# triode_system_board.net
KiCad netlist of a schematic drawn in EAGLE
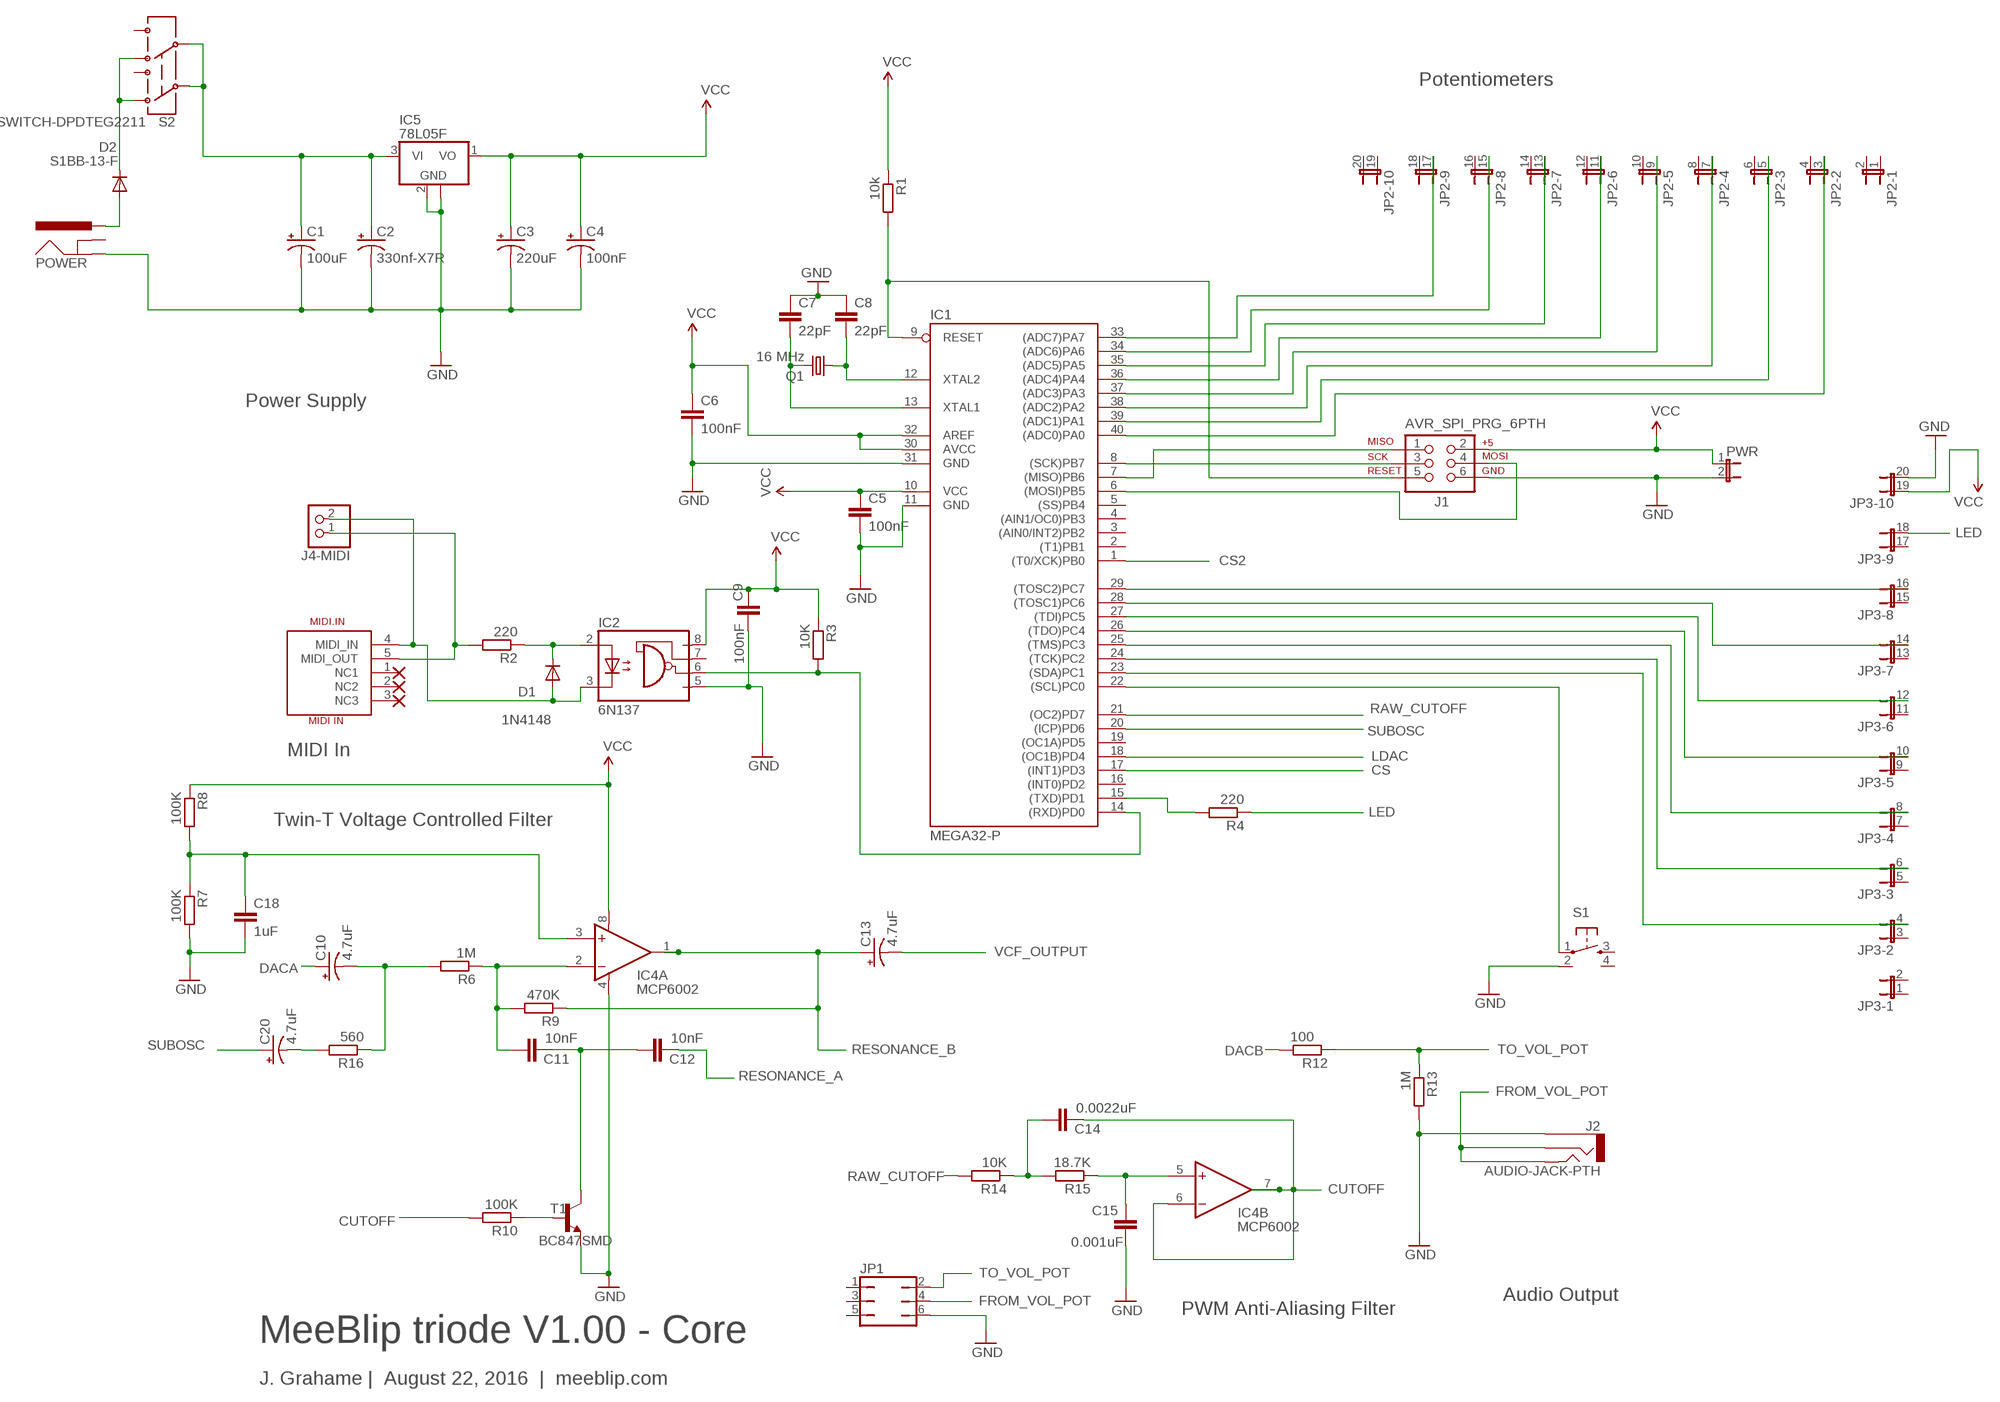
[diagram p0: schematic, sheet 1]
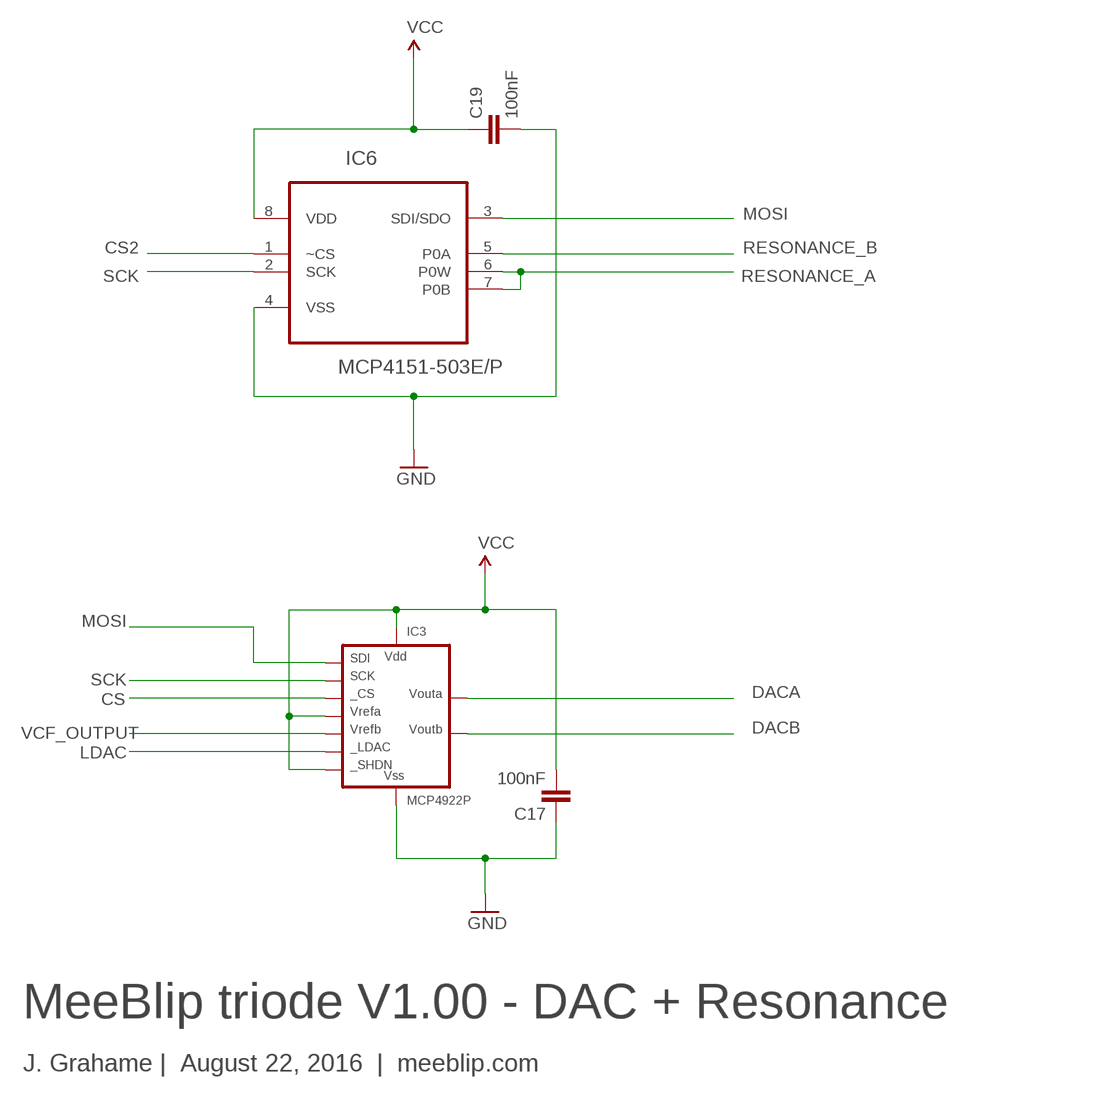
[diagram p1: schematic, sheet 2]

(export (version "E")
  (design (tool "Eeschema 10.0.6"))
  (components
    (comp (ref "C1")
      (value "100uF")
      (footprint "eagle-import:PANASONIC_D")
      (libsource (lib "eagle-import") (part "CAP_POLD"))
    )
    (comp (ref "C2")
      (value "330nf-X7R")
      (footprint "eagle-import:PANASONIC_C")
      (libsource (lib "eagle-import") (part "CAP_POLC"))
    )
    (comp (ref "C3")
      (value "220uF")
      (footprint "eagle-import:PANASONIC_D")
      (libsource (lib "eagle-import") (part "CAP_POLD"))
    )
    (comp (ref "C4")
      (value "100nF")
      (footprint "eagle-import:PANASONIC_C")
      (libsource (lib "eagle-import") (part "CAP_POLC"))
    )
    (comp (ref "C5")
      (value "100nF")
      (footprint "eagle-import:0603-CAP")
      (libsource (lib "eagle-import") (part "CAP0603-CAP"))
    )
    (comp (ref "C6")
      (value "100nF")
      (footprint "eagle-import:0603-CAP")
      (libsource (lib "eagle-import") (part "CAP0603-CAP"))
    )
    (comp (ref "C7")
      (value "22pF")
      (footprint "eagle-import:0603-CAP")
      (libsource (lib "eagle-import") (part "CAP0603-CAP"))
    )
    (comp (ref "C8")
      (value "22pF")
      (footprint "eagle-import:0603-CAP")
      (libsource (lib "eagle-import") (part "CAP0603-CAP"))
    )
    (comp (ref "C9")
      (value "100nF")
      (footprint "eagle-import:0603-CAP")
      (libsource (lib "eagle-import") (part "CAP0603-CAP"))
    )
    (comp (ref "C10")
      (value "4.7uF")
      (footprint "eagle-import:PANASONIC_C")
      (libsource (lib "eagle-import") (part "CAP_POLC"))
    )
    (comp (ref "C11")
      (value "10nF")
      (footprint "eagle-import:0603-CAP")
      (libsource (lib "eagle-import") (part "CAP0603-CAP"))
    )
    (comp (ref "C12")
      (value "10nF")
      (footprint "eagle-import:0603-CAP")
      (libsource (lib "eagle-import") (part "CAP0603-CAP"))
    )
    (comp (ref "C13")
      (value "4.7uF")
      (footprint "eagle-import:PANASONIC_C")
      (libsource (lib "eagle-import") (part "CAP_POLC"))
    )
    (comp (ref "C14")
      (value "0.0022uF")
      (footprint "eagle-import:0603-CAP")
      (libsource (lib "eagle-import") (part "CAP0603-CAP"))
    )
    (comp (ref "C15")
      (value "0.001uF")
      (footprint "eagle-import:0603-CAP")
      (libsource (lib "eagle-import") (part "CAP0603-CAP"))
    )
    (comp (ref "C18")
      (value "1uF")
      (footprint "eagle-import:0603-CAP")
      (libsource (lib "eagle-import") (part "CAP0603-CAP"))
    )
    (comp (ref "C20")
      (value "4.7uF")
      (footprint "eagle-import:PANASONIC_C")
      (libsource (lib "eagle-import") (part "CAP_POLC"))
    )
    (comp (ref "D1")
      (value "1N4148")
      (footprint "eagle-import:SOD123")
      (libsource (lib "eagle-import") (part "DIODE-SOD123"))
    )
    (comp (ref "D2")
      (value "S1BB-13-F")
      (footprint "eagle-import:SMA-DO214AC")
      (libsource (lib "eagle-import") (part "GF1"))
    )
    (comp (ref "IC1")
      (value "MEGA32-P")
      (footprint "eagle-import:DIL40")
      (fields (field (name "MPN") "ATMEGA32-16PU"))
      (libsource (lib "eagle-import") (part "MEGA32-P"))
    )
    (comp (ref "IC2")
      (value "6N137")
      (footprint "eagle-import:DIL08")
      (libsource (lib "eagle-import") (part "6N137"))
    )
    (comp (ref "IC4")
      (value "MCP6002")
      (footprint "eagle-import:DIL08")
      (libsource (lib "eagle-import") (part "MCP6002"))
    )
    (comp (ref "IC5")
      (value "78L05F")
      (footprint "eagle-import:SOT89")
      (libsource (lib "eagle-import") (part "78LF05"))
    )
    (comp (ref "J1")
      (value "AVR_SPI_PRG_6PTH")
      (footprint "eagle-import:2X3")
      (libsource (lib "eagle-import") (part "AVR_SPI_PRG_6PTH"))
    )
    (comp (ref "J2")
      (value "AUDIO-JACK-PTH")
      (footprint "eagle-import:AUDIO-JACK")
      (libsource (lib "eagle-import") (part "AUDIO-JACK-PTH"))
    )
    (comp (ref "J4-MIDI")
      (value "PINHD-1X2")
      (footprint "eagle-import:1X02")
      (libsource (lib "eagle-import") (part "PINHD-1X2"))
    )
    (comp (ref "JP1")
      (value "JP3Q")
      (footprint "eagle-import:JP3Q")
      (libsource (lib "eagle-import") (part "JP3Q"))
    )
    (comp (ref "JP2")
      (value "JP10QE")
      (footprint "eagle-import:JP10Q")
      (libsource (lib "eagle-import") (part "JP10QE"))
    )
    (comp (ref "JP3")
      (value "JP10QE")
      (footprint "eagle-import:JP10Q")
      (libsource (lib "eagle-import") (part "JP10QE"))
    )
    (comp (ref "MIDI.IN")
      (value "MIDI IN")
      (footprint "eagle-import:DIN_5_FEMALE_SUPPORT")
      (libsource (lib "eagle-import") (part "MIDI_CONN_FEMALE_SUPPORT"))
    )
    (comp (ref "POWER")
      (value "POWER_JACKPTH")
      (footprint "eagle-import:POWER_JACK_PTH")
      (libsource (lib "eagle-import") (part "POWER_JACKPTH"))
    )
    (comp (ref "PWR")
      (value "JUMPER-2PTH")
      (footprint "eagle-import:1X02")
      (libsource (lib "eagle-import") (part "JUMPER-2PTH"))
    )
    (comp (ref "Q1")
      (value "16 MHz")
      (footprint "eagle-import:HC49UP")
      (libsource (lib "eagle-import") (part "CRYSTALSMD"))
    )
    (comp (ref "R1")
      (value "10k")
      (footprint "eagle-import:M1206")
      (libsource (lib "eagle-import") (part "R-EU_M1206"))
    )
    (comp (ref "R2")
      (value "220")
      (footprint "eagle-import:M1206")
      (libsource (lib "eagle-import") (part "R-EU_M1206"))
    )
    (comp (ref "R3")
      (value "10K")
      (footprint "eagle-import:M1206")
      (libsource (lib "eagle-import") (part "R-EU_M1206"))
    )
    (comp (ref "R4")
      (value "220")
      (footprint "eagle-import:M1206")
      (libsource (lib "eagle-import") (part "R-EU_M1206"))
    )
    (comp (ref "R6")
      (value "1M")
      (footprint "eagle-import:M1206")
      (libsource (lib "eagle-import") (part "R-EU_M1206"))
    )
    (comp (ref "R7")
      (value "100K")
      (footprint "eagle-import:M1206")
      (libsource (lib "eagle-import") (part "R-EU_M1206"))
    )
    (comp (ref "R8")
      (value "100K")
      (footprint "eagle-import:M1206")
      (libsource (lib "eagle-import") (part "R-EU_M1206"))
    )
    (comp (ref "R9")
      (value "470K")
      (footprint "eagle-import:M1206")
      (libsource (lib "eagle-import") (part "R-EU_M1206"))
    )
    (comp (ref "R10")
      (value "100K")
      (footprint "eagle-import:M1206")
      (libsource (lib "eagle-import") (part "R-EU_M1206"))
    )
    (comp (ref "R12")
      (value "100")
      (footprint "eagle-import:M1206")
      (libsource (lib "eagle-import") (part "R-EU_M1206"))
    )
    (comp (ref "R13")
      (value "1M")
      (footprint "eagle-import:M1206")
      (libsource (lib "eagle-import") (part "R-EU_M1206"))
    )
    (comp (ref "R14")
      (value "10K")
      (footprint "eagle-import:M1206")
      (libsource (lib "eagle-import") (part "R-EU_M1206"))
    )
    (comp (ref "R15")
      (value "18.7K")
      (footprint "eagle-import:M1206")
      (libsource (lib "eagle-import") (part "R-EU_M1206"))
    )
    (comp (ref "R16")
      (value "560")
      (footprint "eagle-import:M1206")
      (libsource (lib "eagle-import") (part "R-EU_M1206"))
    )
    (comp (ref "S1")
      (value "TAC_SWITCHPTH")
      (footprint "eagle-import:TACTILE-PTH")
      (libsource (lib "eagle-import") (part "TAC_SWITCHPTH"))
    )
    (comp (ref "S2")
      (value "SWITCH-DPDTEG2211")
      (footprint "eagle-import:EG2208A")
      (libsource (lib "eagle-import") (part "SWITCH-DPDTEG2211"))
    )
    (comp (ref "T1")
      (value "BC847SMD")
      (footprint "eagle-import:SOT23")
      (libsource (lib "eagle-import") (part "BC847SMD"))
    )
    (comp (ref "C17")
      (value "100nF")
      (footprint "eagle-import:0603-CAP")
      (libsource (lib "eagle-import") (part "CAP0603-CAP"))
    )
    (comp (ref "C19")
      (value "100nF")
      (footprint "eagle-import:0603-CAP")
      (libsource (lib "eagle-import") (part "CAP0603-CAP"))
    )
    (comp (ref "IC3")
      (value "MCP4922P")
      (footprint "eagle-import:DIL14")
      (libsource (lib "eagle-import") (part "MCP4922P"))
    )
    (comp (ref "IC6")
      (value "MCP4151-503E/P")
      (footprint "eagle-import:DIP254P762X533-8")
      (libsource (lib "eagle-import") (part "MCP4151-503E/P"))
    )
  )
  (nets
    (net (code "1") (name "CS") (class "Default")
      (node (ref "IC1") (pin "17") (pinfunction "(INT1)PD3_17") (pintype "bidirectional"))
      (node (ref "IC3") (pin "3") (pinfunction "CS_3") (pintype "input"))
    )
    (net (code "2") (name "CS2") (class "Default")
      (node (ref "IC1") (pin "1") (pinfunction "(T0/XCK)PB0_1") (pintype "bidirectional"))
      (node (ref "IC6") (pin "1") (pinfunction "~{CS}_1") (pintype "input"))
    )
    (net (code "3") (name "CUTOFF") (class "Default")
      (node (ref "C14") (pin "2") (pinfunction "2_2") (pintype "passive"))
      (node (ref "IC4") (pin "6") (pinfunction "-IN_6") (pintype "input"))
      (node (ref "IC4") (pin "7") (pinfunction "OUT_7") (pintype "output"))
      (node (ref "R10") (pin "2") (pinfunction "2_2") (pintype "passive"))
    )
    (net (code "4") (name "DACA") (class "Default")
      (node (ref "C10") (pin "+") (pinfunction "+_+") (pintype "passive"))
      (node (ref "IC3") (pin "14") (pinfunction "VOUTA_14") (pintype "output"))
    )
    (net (code "5") (name "DACB") (class "Default")
      (node (ref "IC3") (pin "10") (pinfunction "VOUTB_10") (pintype "output"))
      (node (ref "R12") (pin "2") (pinfunction "2_2") (pintype "passive"))
    )
    (net (code "6") (name "FROM_VOL_POT") (class "Default")
      (node (ref "J2") (pin "2") (pinfunction "2_2") (pintype "bidirectional"))
      (node (ref "J2") (pin "5") (pinfunction "5_5") (pintype "bidirectional"))
      (node (ref "JP1") (pin "4") (pinfunction "4_4") (pintype "passive"))
    )
    (net (code "7") (name "GND") (class "Default")
      (node (ref "C1") (pin "-") (pinfunction "-_-") (pintype "passive"))
      (node (ref "C15") (pin "2") (pinfunction "2_2") (pintype "passive"))
      (node (ref "C17") (pin "1") (pinfunction "1_1") (pintype "passive"))
      (node (ref "C18") (pin "2") (pinfunction "2_2") (pintype "passive"))
      (node (ref "C19") (pin "2") (pinfunction "2_2") (pintype "passive"))
      (node (ref "C2") (pin "-") (pinfunction "-_-") (pintype "passive"))
      (node (ref "C3") (pin "-") (pinfunction "-_-") (pintype "passive"))
      (node (ref "C4") (pin "-") (pinfunction "-_-") (pintype "passive"))
      (node (ref "C5") (pin "2") (pinfunction "2_2") (pintype "passive"))
      (node (ref "C6") (pin "2") (pinfunction "2_2") (pintype "passive"))
      (node (ref "C7") (pin "1") (pinfunction "1_1") (pintype "passive"))
      (node (ref "C8") (pin "1") (pinfunction "1_1") (pintype "passive"))
      (node (ref "C9") (pin "2") (pinfunction "2_2") (pintype "passive"))
      (node (ref "IC1") (pin "11") (pinfunction "GND_11") (pintype "power_in"))
      (node (ref "IC1") (pin "31") (pinfunction "GND_31") (pintype "power_in"))
      (node (ref "IC2") (pin "5") (pinfunction "GND_5") (pintype "passive"))
      (node (ref "IC3") (pin "12") (pinfunction "VSS_12") (pintype "power_in"))
      (node (ref "IC4") (pin "4") (pinfunction "V-_4") (pintype "power_in"))
      (node (ref "IC5") (pin "2") (pinfunction "GND_2") (pintype "passive"))
      (node (ref "IC5") (pin "2@1") (pinfunction "GND_2@1") (pintype "passive"))
      (node (ref "IC6") (pin "4") (pinfunction "VSS_4") (pintype "power_in"))
      (node (ref "J1") (pin "6") (pinfunction "6_6") (pintype "passive"))
      (node (ref "J2") (pin "1") (pinfunction "1_1") (pintype "bidirectional"))
      (node (ref "JP1") (pin "6") (pinfunction "6_6") (pintype "passive"))
      (node (ref "JP3") (pin "20") (pinfunction "2_20") (pintype "passive"))
      (node (ref "POWER") (pin "GND") (pinfunction "GND_GND") (pintype "bidirectional"))
      (node (ref "PWR") (pin "2") (pinfunction "2_2") (pintype "passive"))
      (node (ref "R13") (pin "2") (pinfunction "2_2") (pintype "passive"))
      (node (ref "R7") (pin "2") (pinfunction "2_2") (pintype "passive"))
      (node (ref "S1") (pin "2") (pinfunction "2_2") (pintype "passive"))
      (node (ref "T1") (pin "2") (pinfunction "E_2") (pintype "passive"))
    )
    (net (code "8") (name "LDAC") (class "Default")
      (node (ref "IC1") (pin "18") (pinfunction "(OC1B)PD4_18") (pintype "bidirectional"))
      (node (ref "IC3") (pin "8") (pinfunction "LDAC_8") (pintype "input"))
    )
    (net (code "9") (name "LED") (class "Default")
      (node (ref "JP3") (pin "18") (pinfunction "2_18") (pintype "passive"))
      (node (ref "R4") (pin "1") (pinfunction "1_1") (pintype "passive"))
    )
    (net (code "10") (name "MOSI") (class "Default")
      (node (ref "IC1") (pin "6") (pinfunction "(MOSI)PB5_6") (pintype "bidirectional"))
      (node (ref "IC3") (pin "5") (pinfunction "SDI_5") (pintype "input"))
      (node (ref "IC6") (pin "3") (pinfunction "SDI/SDO_3") (pintype "bidirectional"))
      (node (ref "J1") (pin "4") (pinfunction "4_4") (pintype "passive"))
    )
    (net (code "11") (name "Net-(C10-Pad-)") (class "Default")
      (node (ref "C10") (pin "-") (pinfunction "-_-") (pintype "passive"))
      (node (ref "R16") (pin "1") (pinfunction "1_1") (pintype "passive"))
      (node (ref "R6") (pin "2") (pinfunction "2_2") (pintype "passive"))
    )
    (net (code "12") (name "Net-(C14-Pad1)") (class "Default")
      (node (ref "C14") (pin "1") (pinfunction "1_1") (pintype "passive"))
      (node (ref "R14") (pin "1") (pinfunction "1_1") (pintype "passive"))
      (node (ref "R15") (pin "2") (pinfunction "2_2") (pintype "passive"))
    )
    (net (code "13") (name "Net-(C20-Pad-)") (class "Default")
      (node (ref "C20") (pin "-") (pinfunction "-_-") (pintype "passive"))
      (node (ref "R16") (pin "2") (pinfunction "2_2") (pintype "passive"))
    )
    (net (code "14") (name "Net-(D2-C)") (class "Default")
      (node (ref "D2") (pin "K") (pinfunction "C_K") (pintype "passive"))
      (node (ref "S2") (pin "P1-TA") (pinfunction "1_P1-TA") (pintype "bidirectional"))
      (node (ref "S2") (pin "P2-TA") (pinfunction "4_P2-TA") (pintype "bidirectional"))
    )
    (net (code "15") (name "Net-(D2-PadA)") (class "Default")
      (node (ref "D2") (pin "A") (pinfunction "A_A") (pintype "passive"))
      (node (ref "POWER") (pin "PWR") (pinfunction "PWR_PWR") (pintype "bidirectional"))
    )
    (net (code "16") (name "Net-(IC1-(ADC0)PA0)") (class "Default")
      (node (ref "IC1") (pin "40") (pinfunction "(ADC0)PA0_40") (pintype "bidirectional"))
      (node (ref "JP2") (pin "3") (pinfunction "1_3") (pintype "passive"))
    )
    (net (code "17") (name "Net-(IC1-(ADC1)PA1)") (class "Default")
      (node (ref "IC1") (pin "39") (pinfunction "(ADC1)PA1_39") (pintype "bidirectional"))
      (node (ref "JP2") (pin "5") (pinfunction "1_5") (pintype "passive"))
    )
    (net (code "18") (name "Net-(IC1-(ADC2)PA2)") (class "Default")
      (node (ref "IC1") (pin "38") (pinfunction "(ADC2)PA2_38") (pintype "bidirectional"))
      (node (ref "JP2") (pin "7") (pinfunction "1_7") (pintype "passive"))
    )
    (net (code "19") (name "Net-(IC1-(ADC3)PA3)") (class "Default")
      (node (ref "IC1") (pin "37") (pinfunction "(ADC3)PA3_37") (pintype "bidirectional"))
      (node (ref "JP2") (pin "9") (pinfunction "1_9") (pintype "passive"))
    )
    (net (code "20") (name "Net-(IC1-(ADC4)PA4)") (class "Default")
      (node (ref "IC1") (pin "36") (pinfunction "(ADC4)PA4_36") (pintype "bidirectional"))
      (node (ref "JP2") (pin "11") (pinfunction "1_11") (pintype "passive"))
    )
    (net (code "21") (name "Net-(IC1-(ADC5)PA5)") (class "Default")
      (node (ref "IC1") (pin "35") (pinfunction "(ADC5)PA5_35") (pintype "bidirectional"))
      (node (ref "JP2") (pin "13") (pinfunction "1_13") (pintype "passive"))
    )
    (net (code "22") (name "Net-(IC1-(ADC6)PA6)") (class "Default")
      (node (ref "IC1") (pin "34") (pinfunction "(ADC6)PA6_34") (pintype "bidirectional"))
      (node (ref "JP2") (pin "15") (pinfunction "1_15") (pintype "passive"))
    )
    (net (code "23") (name "Net-(IC1-(ADC7)PA7)") (class "Default")
      (node (ref "IC1") (pin "33") (pinfunction "(ADC7)PA7_33") (pintype "bidirectional"))
      (node (ref "JP2") (pin "17") (pinfunction "1_17") (pintype "passive"))
    )
    (net (code "24") (name "Net-(IC1-(MISO)PB6)") (class "Default")
      (node (ref "IC1") (pin "7") (pinfunction "(MISO)PB6_7") (pintype "bidirectional"))
      (node (ref "J1") (pin "1") (pinfunction "1_1") (pintype "passive"))
    )
    (net (code "25") (name "Net-(IC1-(RXD)PD0)") (class "Default")
      (node (ref "IC1") (pin "14") (pinfunction "(RXD)PD0_14") (pintype "bidirectional"))
      (node (ref "IC2") (pin "6") (pinfunction "VO_6") (pintype "passive"))
      (node (ref "R3") (pin "2") (pinfunction "2_2") (pintype "passive"))
    )
    (net (code "26") (name "Net-(IC1-(SCL)PC0)") (class "Default")
      (node (ref "IC1") (pin "22") (pinfunction "(SCL)PC0_22") (pintype "bidirectional"))
      (node (ref "S1") (pin "1") (pinfunction "1_1") (pintype "passive"))
    )
    (net (code "27") (name "Net-(IC1-(SDA)PC1)") (class "Default")
      (node (ref "IC1") (pin "23") (pinfunction "(SDA)PC1_23") (pintype "bidirectional"))
      (node (ref "JP3") (pin "4") (pinfunction "2_4") (pintype "passive"))
    )
    (net (code "28") (name "Net-(IC1-(TCK)PC2)") (class "Default")
      (node (ref "IC1") (pin "24") (pinfunction "(TCK)PC2_24") (pintype "bidirectional"))
      (node (ref "JP3") (pin "6") (pinfunction "2_6") (pintype "passive"))
    )
    (net (code "29") (name "Net-(IC1-(TDI)PC5)") (class "Default")
      (node (ref "IC1") (pin "27") (pinfunction "(TDI)PC5_27") (pintype "bidirectional"))
      (node (ref "JP3") (pin "12") (pinfunction "2_12") (pintype "passive"))
    )
    (net (code "30") (name "Net-(IC1-(TDO)PC4)") (class "Default")
      (node (ref "IC1") (pin "26") (pinfunction "(TDO)PC4_26") (pintype "bidirectional"))
      (node (ref "JP3") (pin "10") (pinfunction "2_10") (pintype "passive"))
    )
    (net (code "31") (name "Net-(IC1-(TMS)PC3)") (class "Default")
      (node (ref "IC1") (pin "25") (pinfunction "(TMS)PC3_25") (pintype "bidirectional"))
      (node (ref "JP3") (pin "8") (pinfunction "2_8") (pintype "passive"))
    )
    (net (code "32") (name "Net-(IC1-(TOSC1)PC6)") (class "Default")
      (node (ref "IC1") (pin "28") (pinfunction "(TOSC1)PC6_28") (pintype "bidirectional"))
      (node (ref "JP3") (pin "14") (pinfunction "2_14") (pintype "passive"))
    )
    (net (code "33") (name "Net-(IC1-(TOSC2)PC7)") (class "Default")
      (node (ref "IC1") (pin "29") (pinfunction "(TOSC2)PC7_29") (pintype "bidirectional"))
      (node (ref "JP3") (pin "16") (pinfunction "2_16") (pintype "passive"))
    )
    (net (code "34") (name "Net-(IC1-(TXD)PD1)") (class "Default")
      (node (ref "IC1") (pin "15") (pinfunction "(TXD)PD1_15") (pintype "bidirectional"))
      (node (ref "R4") (pin "2") (pinfunction "2_2") (pintype "passive"))
    )
    (net (code "35") (name "Net-(IC1-RESET)") (class "Default")
      (node (ref "IC1") (pin "9") (pinfunction "RESET_9") (pintype "input"))
      (node (ref "J1") (pin "5") (pinfunction "5_5") (pintype "passive"))
      (node (ref "R1") (pin "2") (pinfunction "2_2") (pintype "passive"))
    )
    (net (code "36") (name "Net-(IC1-XTAL1)") (class "Default")
      (node (ref "C7") (pin "2") (pinfunction "2_2") (pintype "passive"))
      (node (ref "IC1") (pin "13") (pinfunction "XTAL1_13") (pintype "bidirectional"))
      (node (ref "Q1") (pin "2") (pinfunction "2_2") (pintype "passive"))
    )
    (net (code "37") (name "Net-(IC1-XTAL2)") (class "Default")
      (node (ref "C8") (pin "2") (pinfunction "2_2") (pintype "passive"))
      (node (ref "IC1") (pin "12") (pinfunction "XTAL2_12") (pintype "bidirectional"))
      (node (ref "Q1") (pin "1") (pinfunction "1_1") (pintype "passive"))
    )
    (net (code "38") (name "Net-(IC2-A)") (class "Default")
      (node (ref "D1") (pin "C") (pinfunction "C_C") (pintype "passive"))
      (node (ref "IC2") (pin "2") (pinfunction "A_2") (pintype "passive"))
      (node (ref "R2") (pin "1") (pinfunction "1_1") (pintype "passive"))
    )
    (net (code "39") (name "Net-(IC2-C)") (class "Default")
      (node (ref "D1") (pin "A") (pinfunction "A_A") (pintype "passive"))
      (node (ref "IC2") (pin "3") (pinfunction "C_3") (pintype "passive"))
      (node (ref "J4-MIDI") (pin "2") (pinfunction "2_2") (pintype "passive"))
      (node (ref "MIDI.IN") (pin "4") (pinfunction "MIDI_IN_4") (pintype "bidirectional"))
    )
    (net (code "40") (name "Net-(IC4A-+IN)") (class "Default")
      (node (ref "C18") (pin "1") (pinfunction "1_1") (pintype "passive"))
      (node (ref "IC4") (pin "3") (pinfunction "+IN_3") (pintype "input"))
      (node (ref "R7") (pin "1") (pinfunction "1_1") (pintype "passive"))
      (node (ref "R8") (pin "2") (pinfunction "2_2") (pintype "passive"))
    )
    (net (code "41") (name "Net-(IC4A--IN)") (class "Default")
      (node (ref "C11") (pin "1") (pinfunction "1_1") (pintype "passive"))
      (node (ref "IC4") (pin "2") (pinfunction "-IN_2") (pintype "input"))
      (node (ref "R6") (pin "1") (pinfunction "1_1") (pintype "passive"))
      (node (ref "R9") (pin "2") (pinfunction "2_2") (pintype "passive"))
    )
    (net (code "42") (name "Net-(IC4B-+IN)") (class "Default")
      (node (ref "C15") (pin "1") (pinfunction "1_1") (pintype "passive"))
      (node (ref "IC4") (pin "5") (pinfunction "+IN_5") (pintype "input"))
      (node (ref "R15") (pin "1") (pinfunction "1_1") (pintype "passive"))
    )
    (net (code "43") (name "Net-(IC5-VI)") (class "Default")
      (node (ref "C1") (pin "+") (pinfunction "+_+") (pintype "passive"))
      (node (ref "C2") (pin "+") (pinfunction "+_+") (pintype "passive"))
      (node (ref "IC5") (pin "3") (pinfunction "VI_3") (pintype "input"))
      (node (ref "S2") (pin "P1") (pinfunction "2_P1") (pintype "bidirectional"))
      (node (ref "S2") (pin "P2") (pinfunction "5_P2") (pintype "bidirectional"))
    )
    (net (code "44") (name "Net-(MIDI.IN-MIDI_OUT)") (class "Default")
      (node (ref "J4-MIDI") (pin "1") (pinfunction "1_1") (pintype "passive"))
      (node (ref "MIDI.IN") (pin "5") (pinfunction "MIDI_OUT_5") (pintype "bidirectional"))
      (node (ref "R2") (pin "2") (pinfunction "2_2") (pintype "passive"))
    )
    (net (code "45") (name "Net-(T1-B)") (class "Default")
      (node (ref "R10") (pin "1") (pinfunction "1_1") (pintype "passive"))
      (node (ref "T1") (pin "1") (pinfunction "B_1") (pintype "passive"))
    )
    (net (code "46") (name "Net-(T1-C)") (class "Default")
      (node (ref "C11") (pin "2") (pinfunction "2_2") (pintype "passive"))
      (node (ref "C12") (pin "1") (pinfunction "1_1") (pintype "passive"))
      (node (ref "T1") (pin "3") (pinfunction "C_3") (pintype "passive"))
    )
    (net (code "47") (name "RAW_CUTOFF") (class "Default")
      (node (ref "IC1") (pin "21") (pinfunction "(OC2)PD7_21") (pintype "bidirectional"))
      (node (ref "R14") (pin "2") (pinfunction "2_2") (pintype "passive"))
    )
    (net (code "48") (name "RESONANCE_A") (class "Default")
      (node (ref "C12") (pin "2") (pinfunction "2_2") (pintype "passive"))
      (node (ref "IC6") (pin "6") (pinfunction "P0W_6") (pintype "passive"))
      (node (ref "IC6") (pin "7") (pinfunction "P0B_7") (pintype "passive"))
    )
    (net (code "49") (name "RESONANCE_B") (class "Default")
      (node (ref "C13") (pin "+") (pinfunction "+_+") (pintype "passive"))
      (node (ref "IC4") (pin "1") (pinfunction "OUT_1") (pintype "output"))
      (node (ref "IC6") (pin "5") (pinfunction "P0A_5") (pintype "passive"))
      (node (ref "R9") (pin "1") (pinfunction "1_1") (pintype "passive"))
    )
    (net (code "50") (name "SCK") (class "Default")
      (node (ref "IC1") (pin "8") (pinfunction "(SCK)PB7_8") (pintype "bidirectional"))
      (node (ref "IC3") (pin "4") (pinfunction "SCK_4") (pintype "input"))
      (node (ref "IC6") (pin "2") (pinfunction "SCK_2") (pintype "input"))
      (node (ref "J1") (pin "3") (pinfunction "3_3") (pintype "passive"))
    )
    (net (code "51") (name "SUBOSC") (class "Default")
      (node (ref "C20") (pin "+") (pinfunction "+_+") (pintype "passive"))
      (node (ref "IC1") (pin "20") (pinfunction "(ICP)PD6_20") (pintype "bidirectional"))
    )
    (net (code "52") (name "TO_VOL_POT") (class "Default")
      (node (ref "JP1") (pin "2") (pinfunction "2_2") (pintype "passive"))
      (node (ref "R12") (pin "1") (pinfunction "1_1") (pintype "passive"))
      (node (ref "R13") (pin "1") (pinfunction "1_1") (pintype "passive"))
    )
    (net (code "53") (name "VCC") (class "Default")
      (node (ref "C17") (pin "2") (pinfunction "2_2") (pintype "passive"))
      (node (ref "C19") (pin "1") (pinfunction "1_1") (pintype "passive"))
      (node (ref "C3") (pin "+") (pinfunction "+_+") (pintype "passive"))
      (node (ref "C4") (pin "+") (pinfunction "+_+") (pintype "passive"))
      (node (ref "C5") (pin "1") (pinfunction "1_1") (pintype "passive"))
      (node (ref "C6") (pin "1") (pinfunction "1_1") (pintype "passive"))
      (node (ref "C9") (pin "1") (pinfunction "1_1") (pintype "passive"))
      (node (ref "IC1") (pin "10") (pinfunction "VCC_10") (pintype "power_in"))
      (node (ref "IC1") (pin "30") (pinfunction "AVCC_30") (pintype "power_in"))
      (node (ref "IC1") (pin "32") (pinfunction "AREF_32") (pintype "passive"))
      (node (ref "IC2") (pin "8") (pinfunction "VCC_8") (pintype "passive"))
      (node (ref "IC3") (pin "1") (pinfunction "VDD_1") (pintype "power_in"))
      (node (ref "IC3") (pin "13") (pinfunction "VREFA_13") (pintype "input"))
      (node (ref "IC3") (pin "9") (pinfunction "SHDN_9") (pintype "input"))
      (node (ref "IC4") (pin "8") (pinfunction "V+_8") (pintype "power_in"))
      (node (ref "IC5") (pin "1") (pinfunction "VO_1") (pintype "passive"))
      (node (ref "IC6") (pin "8") (pinfunction "VDD_8") (pintype "power_in"))
      (node (ref "J1") (pin "2") (pinfunction "2_2") (pintype "passive"))
      (node (ref "JP3") (pin "19") (pinfunction "1_19") (pintype "passive"))
      (node (ref "PWR") (pin "1") (pinfunction "1_1") (pintype "passive"))
      (node (ref "R1") (pin "1") (pinfunction "1_1") (pintype "passive"))
      (node (ref "R3") (pin "1") (pinfunction "1_1") (pintype "passive"))
      (node (ref "R8") (pin "1") (pinfunction "1_1") (pintype "passive"))
    )
    (net (code "54") (name "VCF_OUTPUT") (class "Default")
      (node (ref "C13") (pin "-") (pinfunction "-_-") (pintype "passive"))
      (node (ref "IC3") (pin "11") (pinfunction "VREFB_11") (pintype "input"))
    )
    (net (code "55") (name "unconnected-(IC1-(AIN0{slash}INT2)PB2-Pad3)") (class "Default")
      (node (ref "IC1") (pin "3") (pinfunction "(AIN0/INT2)PB2_3") (pintype "bidirectional"))
    )
    (net (code "56") (name "unconnected-(IC1-(AIN1{slash}OC0)PB3-Pad4)") (class "Default")
      (node (ref "IC1") (pin "4") (pinfunction "(AIN1/OC0)PB3_4") (pintype "bidirectional"))
    )
    (net (code "57") (name "unconnected-(IC1-(INT0)PD2-Pad16)") (class "Default")
      (node (ref "IC1") (pin "16") (pinfunction "(INT0)PD2_16") (pintype "bidirectional"))
    )
    (net (code "58") (name "unconnected-(IC1-(OC1A)PD5-Pad19)") (class "Default")
      (node (ref "IC1") (pin "19") (pinfunction "(OC1A)PD5_19") (pintype "bidirectional"))
    )
    (net (code "59") (name "unconnected-(IC1-(SS)PB4-Pad5)") (class "Default")
      (node (ref "IC1") (pin "5") (pinfunction "(SS)PB4_5") (pintype "bidirectional"))
    )
    (net (code "60") (name "unconnected-(IC1-(T1)PB1-Pad2)") (class "Default")
      (node (ref "IC1") (pin "2") (pinfunction "(T1)PB1_2") (pintype "bidirectional"))
    )
    (net (code "61") (name "unconnected-(IC2-VE-Pad7)") (class "Default")
      (node (ref "IC2") (pin "7") (pinfunction "VE_7") (pintype "passive"))
    )
    (net (code "62") (name "unconnected-(JP1-Pad1)") (class "Default")
      (node (ref "JP1") (pin "1") (pinfunction "1_1") (pintype "passive"))
    )
    (net (code "63") (name "unconnected-(JP1-Pad3)") (class "Default")
      (node (ref "JP1") (pin "3") (pinfunction "3_3") (pintype "passive"))
    )
    (net (code "64") (name "unconnected-(JP1-Pad5)") (class "Default")
      (node (ref "JP1") (pin "5") (pinfunction "5_5") (pintype "passive"))
    )
    (net (code "65") (name "unconnected-(JP2-Pad1)") (class "Default")
      (node (ref "JP2") (pin "1") (pinfunction "1_1") (pintype "passive"))
    )
    (net (code "66") (name "unconnected-(JP2-Pad2)") (class "Default")
      (node (ref "JP2") (pin "2") (pinfunction "2_2") (pintype "passive"))
    )
    (net (code "67") (name "unconnected-(JP2B-1-Pad19)") (class "Default")
      (node (ref "JP2") (pin "19") (pinfunction "1_19") (pintype "passive"))
    )
    (net (code "68") (name "unconnected-(JP2B-2-Pad20)") (class "Default")
      (node (ref "JP2") (pin "20") (pinfunction "2_20") (pintype "passive"))
    )
    (net (code "69") (name "unconnected-(JP2C-2-Pad4)") (class "Default")
      (node (ref "JP2") (pin "4") (pinfunction "2_4") (pintype "passive"))
    )
    (net (code "70") (name "unconnected-(JP2D-2-Pad6)") (class "Default")
      (node (ref "JP2") (pin "6") (pinfunction "2_6") (pintype "passive"))
    )
    (net (code "71") (name "unconnected-(JP2E-2-Pad8)") (class "Default")
      (node (ref "JP2") (pin "8") (pinfunction "2_8") (pintype "passive"))
    )
    (net (code "72") (name "unconnected-(JP2F-2-Pad10)") (class "Default")
      (node (ref "JP2") (pin "10") (pinfunction "2_10") (pintype "passive"))
    )
    (net (code "73") (name "unconnected-(JP2G-2-Pad12)") (class "Default")
      (node (ref "JP2") (pin "12") (pinfunction "2_12") (pintype "passive"))
    )
    (net (code "74") (name "unconnected-(JP2H-2-Pad14)") (class "Default")
      (node (ref "JP2") (pin "14") (pinfunction "2_14") (pintype "passive"))
    )
    (net (code "75") (name "unconnected-(JP2I-2-Pad16)") (class "Default")
      (node (ref "JP2") (pin "16") (pinfunction "2_16") (pintype "passive"))
    )
    (net (code "76") (name "unconnected-(JP2J-2-Pad18)") (class "Default")
      (node (ref "JP2") (pin "18") (pinfunction "2_18") (pintype "passive"))
    )
    (net (code "77") (name "unconnected-(JP3-Pad1)") (class "Default")
      (node (ref "JP3") (pin "1") (pinfunction "1_1") (pintype "passive"))
    )
    (net (code "78") (name "unconnected-(JP3-Pad2)") (class "Default")
      (node (ref "JP3") (pin "2") (pinfunction "2_2") (pintype "passive"))
    )
    (net (code "79") (name "unconnected-(JP3C-1-Pad3)") (class "Default")
      (node (ref "JP3") (pin "3") (pinfunction "1_3") (pintype "passive"))
    )
    (net (code "80") (name "unconnected-(JP3D-1-Pad5)") (class "Default")
      (node (ref "JP3") (pin "5") (pinfunction "1_5") (pintype "passive"))
    )
    (net (code "81") (name "unconnected-(JP3E-1-Pad7)") (class "Default")
      (node (ref "JP3") (pin "7") (pinfunction "1_7") (pintype "passive"))
    )
    (net (code "82") (name "unconnected-(JP3F-1-Pad9)") (class "Default")
      (node (ref "JP3") (pin "9") (pinfunction "1_9") (pintype "passive"))
    )
    (net (code "83") (name "unconnected-(JP3G-1-Pad11)") (class "Default")
      (node (ref "JP3") (pin "11") (pinfunction "1_11") (pintype "passive"))
    )
    (net (code "84") (name "unconnected-(JP3H-1-Pad13)") (class "Default")
      (node (ref "JP3") (pin "13") (pinfunction "1_13") (pintype "passive"))
    )
    (net (code "85") (name "unconnected-(JP3I-1-Pad15)") (class "Default")
      (node (ref "JP3") (pin "15") (pinfunction "1_15") (pintype "passive"))
    )
    (net (code "86") (name "unconnected-(JP3J-1-Pad17)") (class "Default")
      (node (ref "JP3") (pin "17") (pinfunction "1_17") (pintype "passive"))
    )
    (net (code "87") (name "unconnected-(MIDI.IN-NC1-Pad1)") (class "Default")
      (node (ref "MIDI.IN") (pin "1") (pinfunction "NC1_1") (pintype "bidirectional"))
    )
    (net (code "88") (name "unconnected-(MIDI.IN-NC2-Pad2)") (class "Default")
      (node (ref "MIDI.IN") (pin "2") (pinfunction "NC2_2") (pintype "bidirectional"))
    )
    (net (code "89") (name "unconnected-(MIDI.IN-NC3-Pad3)") (class "Default")
      (node (ref "MIDI.IN") (pin "3") (pinfunction "NC3_3") (pintype "bidirectional"))
    )
    (net (code "90") (name "unconnected-(POWER-PadGNDBREAK)") (class "Default")
      (node (ref "POWER") (pin "GNDBREAK") (pinfunction "GNDBREAK_GNDBREAK") (pintype "bidirectional"))
    )
    (net (code "91") (name "unconnected-(S1-Pad3)") (class "Default")
      (node (ref "S1") (pin "3") (pinfunction "3_3") (pintype "passive"))
    )
    (net (code "92") (name "unconnected-(S1-Pad4)") (class "Default")
      (node (ref "S1") (pin "4") (pinfunction "4_4") (pintype "passive"))
    )
    (net (code "93") (name "unconnected-(S2-3-PadP1-TB)") (class "Default")
      (node (ref "S2") (pin "P1-TB") (pinfunction "3_P1-TB") (pintype "bidirectional"))
    )
    (net (code "94") (name "unconnected-(S2-6-PadP2-TB)") (class "Default")
      (node (ref "S2") (pin "P2-TB") (pinfunction "6_P2-TB") (pintype "bidirectional"))
    )
  )
)
